# Power_Supply.net
KiCad netlist of a schematic drawn in Altium Designer
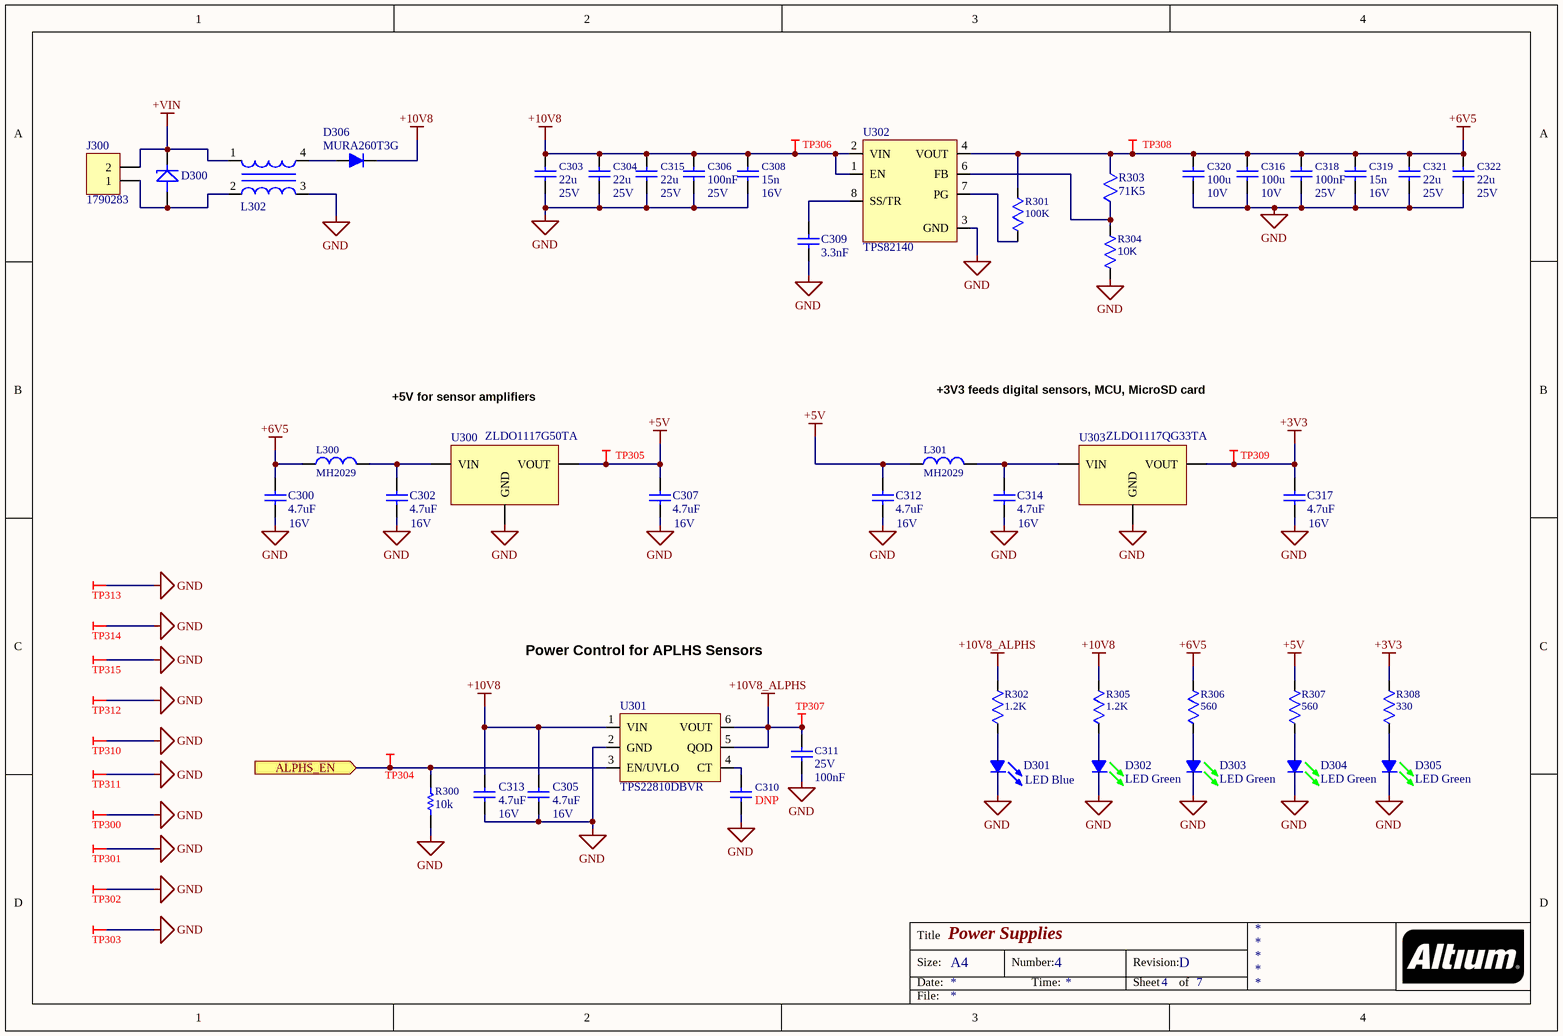
[diagram p0: Power Supply.SchDoc]

(export (version "E")
  (design (tool "Eeschema 10.0.6"))
  (components
    (comp (ref "C300")
      (value "4.7uF")
      (footprint "C1005[0402]")
      (description "Cap,4.7uF,16V,20%,X5R,0402")
      (fields
        (field (name "MANUFACTURER PART NUMBER") "CL05A475MO5NUNC")
        (field (name "MANUFACTURER") "Samsung Electro-Mechanics")
        (field (name "VOLTAGE") "16V")
      )
      (libsource (lib "Capacitors") (part "4.7uF_0402_16V"))
    )
    (comp (ref "C302")
      (value "4.7uF")
      (footprint "C1005[0402]")
      (description "Cap,4.7uF,16V,20%,X5R,0402")
      (fields
        (field (name "MANUFACTURER PART NUMBER") "CL05A475MO5NUNC")
        (field (name "MANUFACTURER") "Samsung Electro-Mechanics")
        (field (name "VOLTAGE") "16V")
      )
      (libsource (lib "Capacitors") (part "4.7uF_0402_16V"))
    )
    (comp (ref "C303")
      (value "22u")
      (footprint "CAPC2012X14N")
      (fields
        (field (name "VOLTAGE") "25V")
        (field (name "MANUFACTURER PART NUMBER") "GRM21BR61E226ME44K")
        (field (name "MANUFACTURER") "Murata")
      )
      (libsource (lib "Capacitors") (part "4.7uF_0603_10V"))
    )
    (comp (ref "C304")
      (value "22u")
      (footprint "CAPC2012X14N")
      (fields
        (field (name "VOLTAGE") "25V")
        (field (name "MANUFACTURER PART NUMBER") "GRM21BR61E226ME44K")
        (field (name "MANUFACTURER") "Murata")
      )
      (libsource (lib "Capacitors") (part "4.7uF_0603_10V"))
    )
    (comp (ref "C305")
      (value "4.7uF")
      (footprint "C1005[0402]")
      (description "Cap,4.7uF,16V,20%,X5R,0402")
      (fields
        (field (name "MANUFACTURER PART NUMBER") "CL05A475MO5NUNC")
        (field (name "MANUFACTURER") "Samsung Electro-Mechanics")
        (field (name "VOLTAGE") "16V")
      )
      (libsource (lib "Capacitors") (part "4.7uF_0402_16V"))
    )
    (comp (ref "C306")
      (value "100nF")
      (footprint "CAPC1005X06N")
      (fields
        (field (name "VOLTAGE") "25V")
        (field (name "MANUFACTURER PART NUMBER") "CL05A104KA5NNNC")
        (field (name "MANUFACTURER") "Samsung")
        (field (name "Comment") "4.7uF")
      )
      (libsource (lib "Capacitors") (part "4.7uF_0603_10V"))
    )
    (comp (ref "C307")
      (value "4.7uF")
      (footprint "C1005[0402]")
      (description "Cap,4.7uF,16V,20%,X5R,0402")
      (fields
        (field (name "MANUFACTURER PART NUMBER") "CL05A475MO5NUNC")
        (field (name "MANUFACTURER") "Samsung Electro-Mechanics")
        (field (name "VOLTAGE") "16V")
      )
      (libsource (lib "Capacitors") (part "4.7uF_0402_16V"))
    )
    (comp (ref "C308")
      (value "15n")
      (footprint "CAPC1005X06N")
      (fields
        (field (name "VOLTAGE") "16V")
        (field (name "MANUFACTURER PART NUMBER") "CL05B153KO5NNNC")
        (field (name "MANUFACTURER") "Samsung")
        (field (name "Comment") "4.7uF")
      )
      (libsource (lib "Capacitors") (part "4.7uF_0603_10V"))
    )
    (comp (ref "C309")
      (value "3.3nF")
      (footprint "C1608[0603]")
      (description "Cap,3.3nF,50V,10%,X7R,0603")
      (fields
        (field (name "MANUFACTURER") "Samsung")
        (field (name "MANUFACTURER PART NUMBER") "CL10B332KB8NNNC")
      )
      (libsource (lib "Capacitors") (part "3.3nF_0603_50V"))
    )
    (comp (ref "C310")
      (value "DNP")
      (footprint "CAPC1005X06N")
      (fields (field (name "Comment") "4.7uF"))
      (libsource (lib "Capacitors") (part "4.7uF_0603_10V"))
    )
    (comp (ref "C311")
      (value "100nF")
      (footprint "CAPC1005X06N")
      (fields
        (field (name "VOLTAGE") "25V")
        (field (name "MANUFACTURER PART NUMBER") "CL05A104KA5NNNC")
        (field (name "MANUFACTURER") "Samsung")
        (field (name "Comment") "4.7uF")
      )
      (libsource (lib "Capacitors") (part "4.7uF_0603_10V"))
    )
    (comp (ref "C312")
      (value "4.7uF")
      (footprint "C1005[0402]")
      (description "Cap,4.7uF,16V,20%,X5R,0402")
      (fields
        (field (name "MANUFACTURER PART NUMBER") "CL05A475MO5NUNC")
        (field (name "MANUFACTURER") "Samsung Electro-Mechanics")
        (field (name "VOLTAGE") "16V")
      )
      (libsource (lib "Capacitors") (part "4.7uF_0402_16V"))
    )
    (comp (ref "C313")
      (value "4.7uF")
      (footprint "C1005[0402]")
      (description "Cap,4.7uF,16V,20%,X5R,0402")
      (fields
        (field (name "MANUFACTURER PART NUMBER") "CL05A475MO5NUNC")
        (field (name "MANUFACTURER") "Samsung Electro-Mechanics")
        (field (name "VOLTAGE") "16V")
      )
      (libsource (lib "Capacitors") (part "4.7uF_0402_16V"))
    )
    (comp (ref "C314")
      (value "4.7uF")
      (footprint "C1005[0402]")
      (description "Cap,4.7uF,16V,20%,X5R,0402")
      (fields
        (field (name "MANUFACTURER PART NUMBER") "CL05A475MO5NUNC")
        (field (name "MANUFACTURER") "Samsung Electro-Mechanics")
        (field (name "VOLTAGE") "16V")
      )
      (libsource (lib "Capacitors") (part "4.7uF_0402_16V"))
    )
    (comp (ref "C315")
      (value "22u")
      (footprint "CAPC2012X14N")
      (fields
        (field (name "VOLTAGE") "25V")
        (field (name "MANUFACTURER PART NUMBER") "GRM21BR61E226ME44K")
        (field (name "MANUFACTURER") "Murata")
      )
      (libsource (lib "Capacitors") (part "4.7uF_0603_10V"))
    )
    (comp (ref "C316")
      (value "100u")
      (footprint "C3225[1210]_Tall")
      (fields
        (field (name "VOLTAGE") "10V")
        (field (name "MANUFACTURER PART NUMBER") "GRM32ER61A107ME20L")
        (field (name "MANUFACTURER") "Murata")
        (field (name "Comment") "4.7uF")
      )
      (libsource (lib "Capacitors") (part "4.7uF_0603_10V"))
    )
    (comp (ref "C317")
      (value "4.7uF")
      (footprint "C1005[0402]")
      (description "Cap,4.7uF,16V,20%,X5R,0402")
      (fields
        (field (name "MANUFACTURER PART NUMBER") "CL05A475MO5NUNC")
        (field (name "MANUFACTURER") "Samsung Electro-Mechanics")
        (field (name "VOLTAGE") "16V")
      )
      (libsource (lib "Capacitors") (part "4.7uF_0402_16V"))
    )
    (comp (ref "C318")
      (value "100nF")
      (footprint "CAPC1005X06N")
      (fields
        (field (name "VOLTAGE") "25V")
        (field (name "MANUFACTURER PART NUMBER") "CL05A104KA5NNNC")
        (field (name "MANUFACTURER") "Samsung")
        (field (name "Comment") "4.7uF")
      )
      (libsource (lib "Capacitors") (part "4.7uF_0603_10V"))
    )
    (comp (ref "C319")
      (value "15n")
      (footprint "CAPC1005X06N")
      (fields
        (field (name "VOLTAGE") "16V")
        (field (name "MANUFACTURER PART NUMBER") "CL05B153KO5NNNC")
        (field (name "MANUFACTURER") "Samsung")
        (field (name "Comment") "4.7uF")
      )
      (libsource (lib "Capacitors") (part "4.7uF_0603_10V"))
    )
    (comp (ref "C320")
      (value "100u")
      (footprint "C3225[1210]_Tall")
      (fields
        (field (name "VOLTAGE") "10V")
        (field (name "MANUFACTURER PART NUMBER") "GRM32ER61A107ME20L")
        (field (name "MANUFACTURER") "Murata")
        (field (name "Comment") "4.7uF")
      )
      (libsource (lib "Capacitors") (part "4.7uF_0603_10V"))
    )
    (comp (ref "C321")
      (value "22u")
      (footprint "CAPC2012X14N")
      (fields
        (field (name "VOLTAGE") "25V")
        (field (name "MANUFACTURER PART NUMBER") "GRM21BR61E226ME44K")
        (field (name "MANUFACTURER") "Murata")
      )
      (libsource (lib "Capacitors") (part "4.7uF_0603_10V"))
    )
    (comp (ref "C322")
      (value "22u")
      (footprint "CAPC2012X14N")
      (fields
        (field (name "VOLTAGE") "25V")
        (field (name "MANUFACTURER PART NUMBER") "GRM21BR61E226ME44K")
        (field (name "MANUFACTURER") "Murata")
      )
      (libsource (lib "Capacitors") (part "4.7uF_0603_10V"))
    )
    (comp (ref "D300")
      (value "12V TVS")
      (footprint "NXP PTVSxS1UR-Series (SOD123W)")
      (fields
        (field (name "MANUFACTURER") "Nexperia")
        (field (name "MANUFACTURER PART NUMBER") "PTVS12VS1UR,115")
      )
      (libsource (lib "FSM_2018") (part "NXP PTVSxS1UR-Series"))
    )
    (comp (ref "D301")
      (value "SMLE12BC7TT86")
      (footprint "LED_0603")
      (description "LED Blue Diffused 0603")
      (fields (field (name "MANUFACTURER") "Rohm"))
      (libsource (lib "Gas Monitor Components") (part "SMLE12BC7TT86"))
    )
    (comp (ref "D302")
      (value "LED Green")
      (footprint "LED_0603")
      (description "LED Green Diffused 0603")
      (fields (field (name "MANUFACTURER") "Rohm") (field (name "MANUFACTURER PART NUMBER") "SML-D12M8WT86"))
      (libsource (lib "LEDs") (part "Green LED"))
    )
    (comp (ref "D303")
      (value "LED Green")
      (footprint "LED_0603")
      (description "LED Green Diffused 0603")
      (fields (field (name "MANUFACTURER") "Rohm") (field (name "MANUFACTURER PART NUMBER") "SML-D12M8WT86"))
      (libsource (lib "LEDs") (part "Green LED"))
    )
    (comp (ref "D304")
      (value "LED Green")
      (footprint "LED_0603")
      (description "LED Green Diffused 0603")
      (fields (field (name "MANUFACTURER") "Rohm") (field (name "MANUFACTURER PART NUMBER") "SML-D12M8WT86"))
      (libsource (lib "LEDs") (part "Green LED"))
    )
    (comp (ref "D305")
      (value "LED Green")
      (footprint "LED_0603")
      (description "LED Green Diffused 0603")
      (fields (field (name "MANUFACTURER") "Rohm") (field (name "MANUFACTURER PART NUMBER") "SML-D12M8WT86"))
      (libsource (lib "LEDs") (part "Green LED"))
    )
    (comp (ref "D306")
      (value "MURA260T3G")
      (footprint "Diode SMA DIOM5226X240N")
      (description "Diode Standard 600V 2A Surface Mount SMA")
      (fields (field (name "MANUFACTURER") "ON Semi") (field (name "MANUFACTURER PART NUMBER") "MURA260T3G"))
      (libsource (lib "Gas Monitor Components") (part "MURA260T3G"))
    )
    (comp (ref "J300")
      (value "1790283")
      (footprint "5.08mm 2pos TermBlock")
      (description "5.08mm Spring Cage, Tension Clamp, Pheonix Contact, 2pos, THD")
      (fields (field (name "MANUFACTURER") "Phoenix Contact"))
      (libsource (lib "Connectors-V") (part "TERM BLOCK 2POS 45DEG 5.08MM"))
    )
    (comp (ref "L300")
      (value "MH2029")
      (footprint "L2012[0805]")
      (description "Ferrite,SMD,3A,30Ohm,0805")
      (fields
        (field (name "MANUFACTURER") "Bourns Inc.")
        (field (name "MANUFACTURER PART NUMBER") "MH2029-300Y")
      )
      (libsource (lib "Inductors") (part "Ferrite_MH2029_0805"))
    )
    (comp (ref "L301")
      (value "MH2029")
      (footprint "L2012[0805]")
      (description "Ferrite,SMD,3A,30Ohm,0805")
      (fields
        (field (name "MANUFACTURER") "Bourns Inc.")
        (field (name "MANUFACTURER PART NUMBER") "MH2029-300Y")
      )
      (libsource (lib "Inductors") (part "Ferrite_MH2029_0805"))
    )
    (comp (ref "L302")
      (value "CM3421Y600R-10")
      (footprint "CM3421Y600R-10")
      (description "2 Line Common Mode Choke Surface Mount 60 Ohms @ 100MHz 15A DCR 0.75mOhm")
      (fields (field (name "MANUFACTURER") "Laird"))
      (libsource (lib "Gas Monitor Components") (part "CM3421Y600R-10"))
    )
    (comp (ref "R300")
      (value "10k")
      (footprint "RESC1005X03N")
      (fields
        (field (name "MANUFACTURER") "Panasonic")
        (field (name "MANUFACTURER PART NUMBER") "ERJ-2RKF1002X")
        (field (name "Comment") "RES: GENERAL")
      )
      (libsource (lib "Santuary") (part "RES{colon} GENERAL"))
    )
    (comp (ref "R301")
      (value "100K")
      (footprint "RESC1005X03N")
      (description "Res,SMD,0603,1/10W,100K,1%")
      (fields
        (field (name "MANUFACTURER") "Panasonic")
        (field (name "MANUFACTURER PART NUMBER") "ERJ-2RKF1003X")
      )
      (libsource (lib "Resistors") (part "100K_0603_0.1W"))
    )
    (comp (ref "R302")
      (value "1.2K")
      (footprint "R1608[0603] small")
      (description "RES 1K Ohm ±5%, 0.25W,1/4W 0603")
      (fields
        (field (name "MANUFACTURER") "Yageo")
        (field (name "MANUFACTURER PART NUMBER") "RC0603FR-071K2L")
      )
      (libsource (lib "Resistors") (part "1K00_0603_0.1W"))
    )
    (comp (ref "R303")
      (value "71K5")
      (footprint "RESC1005X03N")
      (description "RES SMD 71.5K OHM 1% 1/10W 0603")
      (fields
        (field (name "MANUFACTURER PART NUMBER") "ERJ-2RKF7152X")
        (field (name "MANUFACTURER") "Panasonic Electronic Components")
      )
      (libsource (lib "Resistors") (part "71K5_0603_1/10W"))
    )
    (comp (ref "R304")
      (value "10K")
      (footprint "RESC1005X03N")
      (description "RES 1K Ohm ±5%, 0.25W,1/4W 0603")
      (fields
        (field (name "MANUFACTURER") "Panasonic")
        (field (name "MANUFACTURER PART NUMBER") "ERJ-2RKF1002X")
      )
      (libsource (lib "Resistors") (part "1K00_0603_0.1W"))
    )
    (comp (ref "R305")
      (value "1.2K")
      (footprint "R1608[0603] small")
      (description "RES 1K Ohm ±5%, 0.25W,1/4W 0603")
      (fields
        (field (name "MANUFACTURER") "Yageo")
        (field (name "MANUFACTURER PART NUMBER") "RC0603FR-071K2L")
      )
      (libsource (lib "Resistors") (part "1K00_0603_0.1W"))
    )
    (comp (ref "R306")
      (value "560")
      (footprint "R1608[0603] small")
      (description "RES 1K Ohm ±5%, 0.25W,1/4W 0603")
      (fields
        (field (name "MANUFACTURER") "Rohm")
        (field (name "MANUFACTURER PART NUMBER") "RC0603FR-07560RL")
      )
      (libsource (lib "Resistors") (part "1K00_0603_0.1W"))
    )
    (comp (ref "R307")
      (value "560")
      (footprint "R1608[0603] small")
      (description "RES 1K Ohm ±5%, 0.25W,1/4W 0603")
      (fields
        (field (name "MANUFACTURER") "Rohm")
        (field (name "MANUFACTURER PART NUMBER") "RC0603FR-07560RL")
      )
      (libsource (lib "Resistors") (part "1K00_0603_0.1W"))
    )
    (comp (ref "R308")
      (value "330")
      (footprint "R1608[0603] small")
      (description "RES 1K Ohm ±5%, 0.25W,1/4W 0603")
      (fields
        (field (name "MANUFACTURER") "Rohm")
        (field (name "MANUFACTURER PART NUMBER") "RC0603FR-07330RL")
      )
      (libsource (lib "Resistors") (part "1K00_0603_0.1W"))
    )
    (comp (ref "TP300")
      (value "PAD")
      (footprint "TP_SMD_39MIL")
      (description "SMD Test Pad")
      (fields (field (name "MANUFACTURER") "No P/N Required"))
      (libsource (lib "Connectors") (part "TP_SMD_39MIL"))
    )
    (comp (ref "TP301")
      (value "PAD")
      (footprint "TP_SMD_39MIL")
      (description "SMD Test Pad")
      (fields (field (name "MANUFACTURER") "No P/N Required"))
      (libsource (lib "Connectors") (part "TP_SMD_39MIL"))
    )
    (comp (ref "TP302")
      (value "PAD")
      (footprint "TP_SMD_39MIL")
      (description "SMD Test Pad")
      (fields (field (name "MANUFACTURER") "No P/N Required"))
      (libsource (lib "Connectors") (part "TP_SMD_39MIL"))
    )
    (comp (ref "TP303")
      (value "PAD")
      (footprint "TP_SMD_39MIL")
      (description "SMD Test Pad")
      (fields (field (name "MANUFACTURER") "No P/N Required"))
      (libsource (lib "Connectors") (part "TP_SMD_39MIL"))
    )
    (comp (ref "TP304")
      (value "PAD")
      (footprint "TP_SMD_39MIL")
      (description "SMD Test Pad")
      (fields (field (name "MANUFACTURER") "No P/N Required"))
      (libsource (lib "Connectors") (part "TP_SMD_39MIL"))
    )
    (comp (ref "TP305")
      (value "PAD")
      (footprint "TP_SMD_39MIL")
      (description "SMD Test Pad")
      (fields (field (name "MANUFACTURER") "No P/N Required"))
      (libsource (lib "Connectors") (part "TP_SMD_39MIL"))
    )
    (comp (ref "TP306")
      (value "PAD")
      (footprint "TP_SMD_39MIL")
      (description "SMD Test Pad")
      (fields (field (name "MANUFACTURER") "No P/N Required"))
      (libsource (lib "Connectors") (part "TP_SMD_39MIL"))
    )
    (comp (ref "TP307")
      (value "PAD")
      (footprint "TP_SMD_39MIL")
      (description "SMD Test Pad")
      (fields (field (name "MANUFACTURER") "No P/N Required"))
      (libsource (lib "Connectors") (part "TP_SMD_39MIL"))
    )
    (comp (ref "TP308")
      (value "PAD")
      (footprint "TP_SMD_39MIL")
      (description "SMD Test Pad")
      (fields (field (name "MANUFACTURER") "No P/N Required"))
      (libsource (lib "Connectors") (part "TP_SMD_39MIL"))
    )
    (comp (ref "TP309")
      (value "PAD")
      (footprint "TP_SMD_39MIL")
      (description "SMD Test Pad")
      (fields (field (name "MANUFACTURER") "No P/N Required"))
      (libsource (lib "Connectors") (part "TP_SMD_39MIL"))
    )
    (comp (ref "TP310")
      (value "PAD")
      (footprint "TP_SMD_39MIL")
      (description "SMD Test Pad")
      (fields (field (name "MANUFACTURER") "No P/N Required"))
      (libsource (lib "Connectors") (part "TP_SMD_39MIL"))
    )
    (comp (ref "TP311")
      (value "PAD")
      (footprint "TP_SMD_39MIL")
      (description "SMD Test Pad")
      (fields (field (name "MANUFACTURER") "No P/N Required"))
      (libsource (lib "Connectors") (part "TP_SMD_39MIL"))
    )
    (comp (ref "TP312")
      (value "PAD")
      (footprint "TP_SMD_39MIL")
      (description "SMD Test Pad")
      (fields (field (name "MANUFACTURER") "No P/N Required"))
      (libsource (lib "Connectors") (part "TP_SMD_39MIL"))
    )
    (comp (ref "TP313")
      (value "PAD")
      (footprint "TP_SMD_39MIL")
      (description "SMD Test Pad")
      (fields (field (name "MANUFACTURER") "No P/N Required"))
      (libsource (lib "Connectors") (part "TP_SMD_39MIL"))
    )
    (comp (ref "TP314")
      (value "PAD")
      (footprint "TP_SMD_39MIL")
      (description "SMD Test Pad")
      (fields (field (name "MANUFACTURER") "No P/N Required"))
      (libsource (lib "Connectors") (part "TP_SMD_39MIL"))
    )
    (comp (ref "TP315")
      (value "PAD")
      (footprint "TP_SMD_39MIL")
      (description "SMD Test Pad")
      (fields (field (name "MANUFACTURER") "No P/N Required"))
      (libsource (lib "Connectors") (part "TP_SMD_39MIL"))
    )
    (comp (ref "U300")
      (value "ZLDO1117G50TA")
      (footprint "SOT230P700X165-4N")
      (description "1A 3.3V LDO")
      (fields (field (name "MANUFACTURER") "Diodes Incorporated"))
      (libsource (lib "PMIC") (part "ZLDO1117"))
    )
    (comp (ref "U301")
      (value "TPS22810DBVR")
      (footprint "SOT23")
      (description "High Side Load Switch")
      (fields (field (name "MANUFACTURER") "Texas Instruments"))
      (libsource (lib "Gas Monitor Components") (part "TPS22810DBVR"))
    )
    (comp (ref "U302")
      (value "TPS82140")
      (footprint "SIL0008D")
      (description "DC-DC: 0.9-6V 2A output, 3-17V input. Non-isolated.")
      (fields
        (field (name "MANUFACTURER") "Texas Instruments")
        (field (name "MANUFACTURER PART NUMBER") "TPS82140SILT")
      )
      (libsource (lib "Gas Monitor Components") (part "TPS82140"))
    )
    (comp (ref "U303")
      (value "ZLDO1117QG33TA")
      (footprint "SOT230P700X165-4N")
      (description "1A 3.3V LDO")
      (fields (field (name "MANUFACTURER") "Diodes Incorporated"))
      (libsource (lib "PMIC") (part "ZLDO1117"))
    )
  )
  (nets
    (net (code "1") (name "+3V3") (class "Default")
      (node (ref "C317") (pin "2") (pintype "passive"))
      (node (ref "R308") (pin "2") (pintype "passive"))
      (node (ref "TP309") (pin "1") (pintype "passive"))
      (node (ref "U303") (pin "2") (pinfunction "VOUT_2") (pintype "power_in"))
    )
    (net (code "2") (name "+5V") (class "Default")
      (node (ref "C307") (pin "2") (pintype "passive"))
      (node (ref "C312") (pin "2") (pintype "passive"))
      (node (ref "L301") (pin "1") (pintype "passive"))
      (node (ref "R307") (pin "2") (pintype "passive"))
      (node (ref "TP305") (pin "1") (pintype "passive"))
      (node (ref "U300") (pin "2") (pinfunction "VOUT_2") (pintype "power_in"))
    )
    (net (code "3") (name "+6V5") (class "Default")
      (node (ref "C300") (pin "2") (pintype "passive"))
      (node (ref "C316") (pin "1") (pintype "passive"))
      (node (ref "C318") (pin "1") (pintype "passive"))
      (node (ref "C319") (pin "1") (pintype "passive"))
      (node (ref "C320") (pin "1") (pintype "passive"))
      (node (ref "C321") (pin "1") (pintype "passive"))
      (node (ref "C322") (pin "1") (pintype "passive"))
      (node (ref "L300") (pin "1") (pintype "passive"))
      (node (ref "R301") (pin "2") (pintype "passive"))
      (node (ref "R303") (pin "2") (pinfunction "2_2") (pintype "passive"))
      (node (ref "R306") (pin "2") (pintype "passive"))
      (node (ref "TP308") (pin "1") (pintype "passive"))
      (node (ref "U302") (pin "4") (pinfunction "VOUT_4") (pintype "passive"))
    )
    (net (code "4") (name "+10V8") (class "Default")
      (node (ref "C303") (pin "1") (pintype "passive"))
      (node (ref "C304") (pin "1") (pintype "passive"))
      (node (ref "C305") (pin "2") (pintype "passive"))
      (node (ref "C306") (pin "1") (pintype "passive"))
      (node (ref "C308") (pin "1") (pintype "passive"))
      (node (ref "C313") (pin "2") (pintype "passive"))
      (node (ref "C315") (pin "1") (pintype "passive"))
      (node (ref "D306") (pin "1") (pinfunction "K_1") (pintype "passive"))
      (node (ref "R305") (pin "2") (pintype "passive"))
      (node (ref "TP306") (pin "1") (pintype "passive"))
      (node (ref "U301") (pin "1") (pinfunction "VIN_1") (pintype "passive"))
      (node (ref "U302") (pin "1") (pinfunction "EN_1") (pintype "passive"))
      (node (ref "U302") (pin "2") (pinfunction "VIN_2") (pintype "passive"))
    )
    (net (code "5") (name "+10V8_ALPHS") (class "Default")
      (node (ref "C311") (pin "1") (pintype "passive"))
      (node (ref "R302") (pin "2") (pintype "passive"))
      (node (ref "TP307") (pin "1") (pintype "passive"))
      (node (ref "U301") (pin "5") (pinfunction "QOD_5") (pintype "passive"))
      (node (ref "U301") (pin "6") (pinfunction "VOUT_6") (pintype "passive"))
    )
    (net (code "6") (name "+VIN") (class "Default")
      (node (ref "D300") (pin "1") (pinfunction "1_1") (pintype "passive"))
      (node (ref "J300") (pin "2") (pinfunction "2_2") (pintype "passive"))
      (node (ref "L302") (pin "1") (pinfunction "1_1") (pintype "passive"))
    )
    (net (code "7") (name "/ALPHS_EN") (class "Default")
      (node (ref "R300") (pin "1") (pinfunction "1_1") (pintype "passive"))
      (node (ref "TP304") (pin "1") (pintype "passive"))
      (node (ref "U301") (pin "3") (pinfunction "EN/UVLO_3") (pintype "passive"))
    )
    (net (code "8") (name "GND") (class "Default")
      (node (ref "C300") (pin "1") (pintype "passive"))
      (node (ref "C302") (pin "1") (pintype "passive"))
      (node (ref "C303") (pin "2") (pintype "passive"))
      (node (ref "C304") (pin "2") (pintype "passive"))
      (node (ref "C305") (pin "1") (pintype "passive"))
      (node (ref "C306") (pin "2") (pintype "passive"))
      (node (ref "C307") (pin "1") (pintype "passive"))
      (node (ref "C308") (pin "2") (pintype "passive"))
      (node (ref "C309") (pin "1") (pintype "passive"))
      (node (ref "C310") (pin "2") (pintype "passive"))
      (node (ref "C311") (pin "2") (pintype "passive"))
      (node (ref "C312") (pin "1") (pintype "passive"))
      (node (ref "C313") (pin "1") (pintype "passive"))
      (node (ref "C314") (pin "1") (pintype "passive"))
      (node (ref "C315") (pin "2") (pintype "passive"))
      (node (ref "C316") (pin "2") (pintype "passive"))
      (node (ref "C317") (pin "1") (pintype "passive"))
      (node (ref "C318") (pin "2") (pintype "passive"))
      (node (ref "C319") (pin "2") (pintype "passive"))
      (node (ref "C320") (pin "2") (pintype "passive"))
      (node (ref "C321") (pin "2") (pintype "passive"))
      (node (ref "C322") (pin "2") (pintype "passive"))
      (node (ref "D301") (pin "2") (pintype "passive"))
      (node (ref "D302") (pin "2") (pintype "passive"))
      (node (ref "D303") (pin "2") (pintype "passive"))
      (node (ref "D304") (pin "2") (pintype "passive"))
      (node (ref "D305") (pin "2") (pintype "passive"))
      (node (ref "L302") (pin "3") (pinfunction "3_3") (pintype "passive"))
      (node (ref "R300") (pin "2") (pinfunction "2_2") (pintype "passive"))
      (node (ref "R304") (pin "1") (pintype "passive"))
      (node (ref "TP300") (pin "1") (pintype "passive"))
      (node (ref "TP301") (pin "1") (pintype "passive"))
      (node (ref "TP302") (pin "1") (pintype "passive"))
      (node (ref "TP303") (pin "1") (pintype "passive"))
      (node (ref "TP310") (pin "1") (pintype "passive"))
      (node (ref "TP311") (pin "1") (pintype "passive"))
      (node (ref "TP312") (pin "1") (pintype "passive"))
      (node (ref "TP313") (pin "1") (pintype "passive"))
      (node (ref "TP314") (pin "1") (pintype "passive"))
      (node (ref "TP315") (pin "1") (pintype "passive"))
      (node (ref "U300") (pin "1") (pinfunction "GND_1") (pintype "power_in"))
      (node (ref "U301") (pin "2") (pinfunction "GND_2") (pintype "passive"))
      (node (ref "U302") (pin "3") (pinfunction "GND_3") (pintype "passive"))
      (node (ref "U303") (pin "1") (pinfunction "GND_1") (pintype "power_in"))
    )
    (net (code "9") (name "Net-(D300-Pad2)") (class "Default")
      (node (ref "D300") (pin "2") (pinfunction "2_2") (pintype "passive"))
      (node (ref "J300") (pin "1") (pinfunction "1_1") (pintype "passive"))
      (node (ref "L302") (pin "2") (pinfunction "2_2") (pintype "passive"))
    )
    (net (code "10") (name "Net-(D301-Pad1)") (class "Default")
      (node (ref "D301") (pin "1") (pintype "passive"))
      (node (ref "R302") (pin "1") (pintype "passive"))
    )
    (net (code "11") (name "Net-(D302-Pad1)") (class "Default")
      (node (ref "D302") (pin "1") (pintype "passive"))
      (node (ref "R305") (pin "1") (pintype "passive"))
    )
    (net (code "12") (name "Net-(D303-Pad1)") (class "Default")
      (node (ref "D303") (pin "1") (pintype "passive"))
      (node (ref "R306") (pin "1") (pintype "passive"))
    )
    (net (code "13") (name "Net-(D304-Pad1)") (class "Default")
      (node (ref "D304") (pin "1") (pintype "passive"))
      (node (ref "R307") (pin "1") (pintype "passive"))
    )
    (net (code "14") (name "Net-(D305-Pad1)") (class "Default")
      (node (ref "D305") (pin "1") (pintype "passive"))
      (node (ref "R308") (pin "1") (pintype "passive"))
    )
    (net (code "15") (name "Net-(D306-A)") (class "Default")
      (node (ref "D306") (pin "2") (pinfunction "A_2") (pintype "passive"))
      (node (ref "L302") (pin "4") (pinfunction "4_4") (pintype "passive"))
    )
    (net (code "16") (name "Net-(U300-VIN)") (class "Default")
      (node (ref "C302") (pin "2") (pintype "passive"))
      (node (ref "L300") (pin "2") (pintype "passive"))
      (node (ref "U300") (pin "3") (pinfunction "VIN_3") (pintype "power_in"))
    )
    (net (code "17") (name "Net-(U301-CT)") (class "Default")
      (node (ref "C310") (pin "1") (pintype "passive"))
      (node (ref "U301") (pin "4") (pinfunction "CT_4") (pintype "passive"))
    )
    (net (code "18") (name "Net-(U302-FB)") (class "Default")
      (node (ref "R303") (pin "1") (pinfunction "1_1") (pintype "passive"))
      (node (ref "R304") (pin "2") (pintype "passive"))
      (node (ref "U302") (pin "6") (pinfunction "FB_6") (pintype "passive"))
    )
    (net (code "19") (name "Net-(U302-PG)") (class "Default")
      (node (ref "R301") (pin "1") (pintype "passive"))
      (node (ref "U302") (pin "7") (pinfunction "PG_7") (pintype "passive"))
    )
    (net (code "20") (name "Net-(U302-SS{slash}TR)") (class "Default")
      (node (ref "C309") (pin "2") (pintype "passive"))
      (node (ref "U302") (pin "8") (pinfunction "SS/TR_8") (pintype "passive"))
    )
    (net (code "21") (name "Net-(U303-VIN)") (class "Default")
      (node (ref "C314") (pin "2") (pintype "passive"))
      (node (ref "L301") (pin "2") (pintype "passive"))
      (node (ref "U303") (pin "3") (pinfunction "VIN_3") (pintype "power_in"))
    )
  )
)
